# cartePIC_PCR95_8_3_via_res.net
KiCad netlist of a schematic drawn in EAGLE
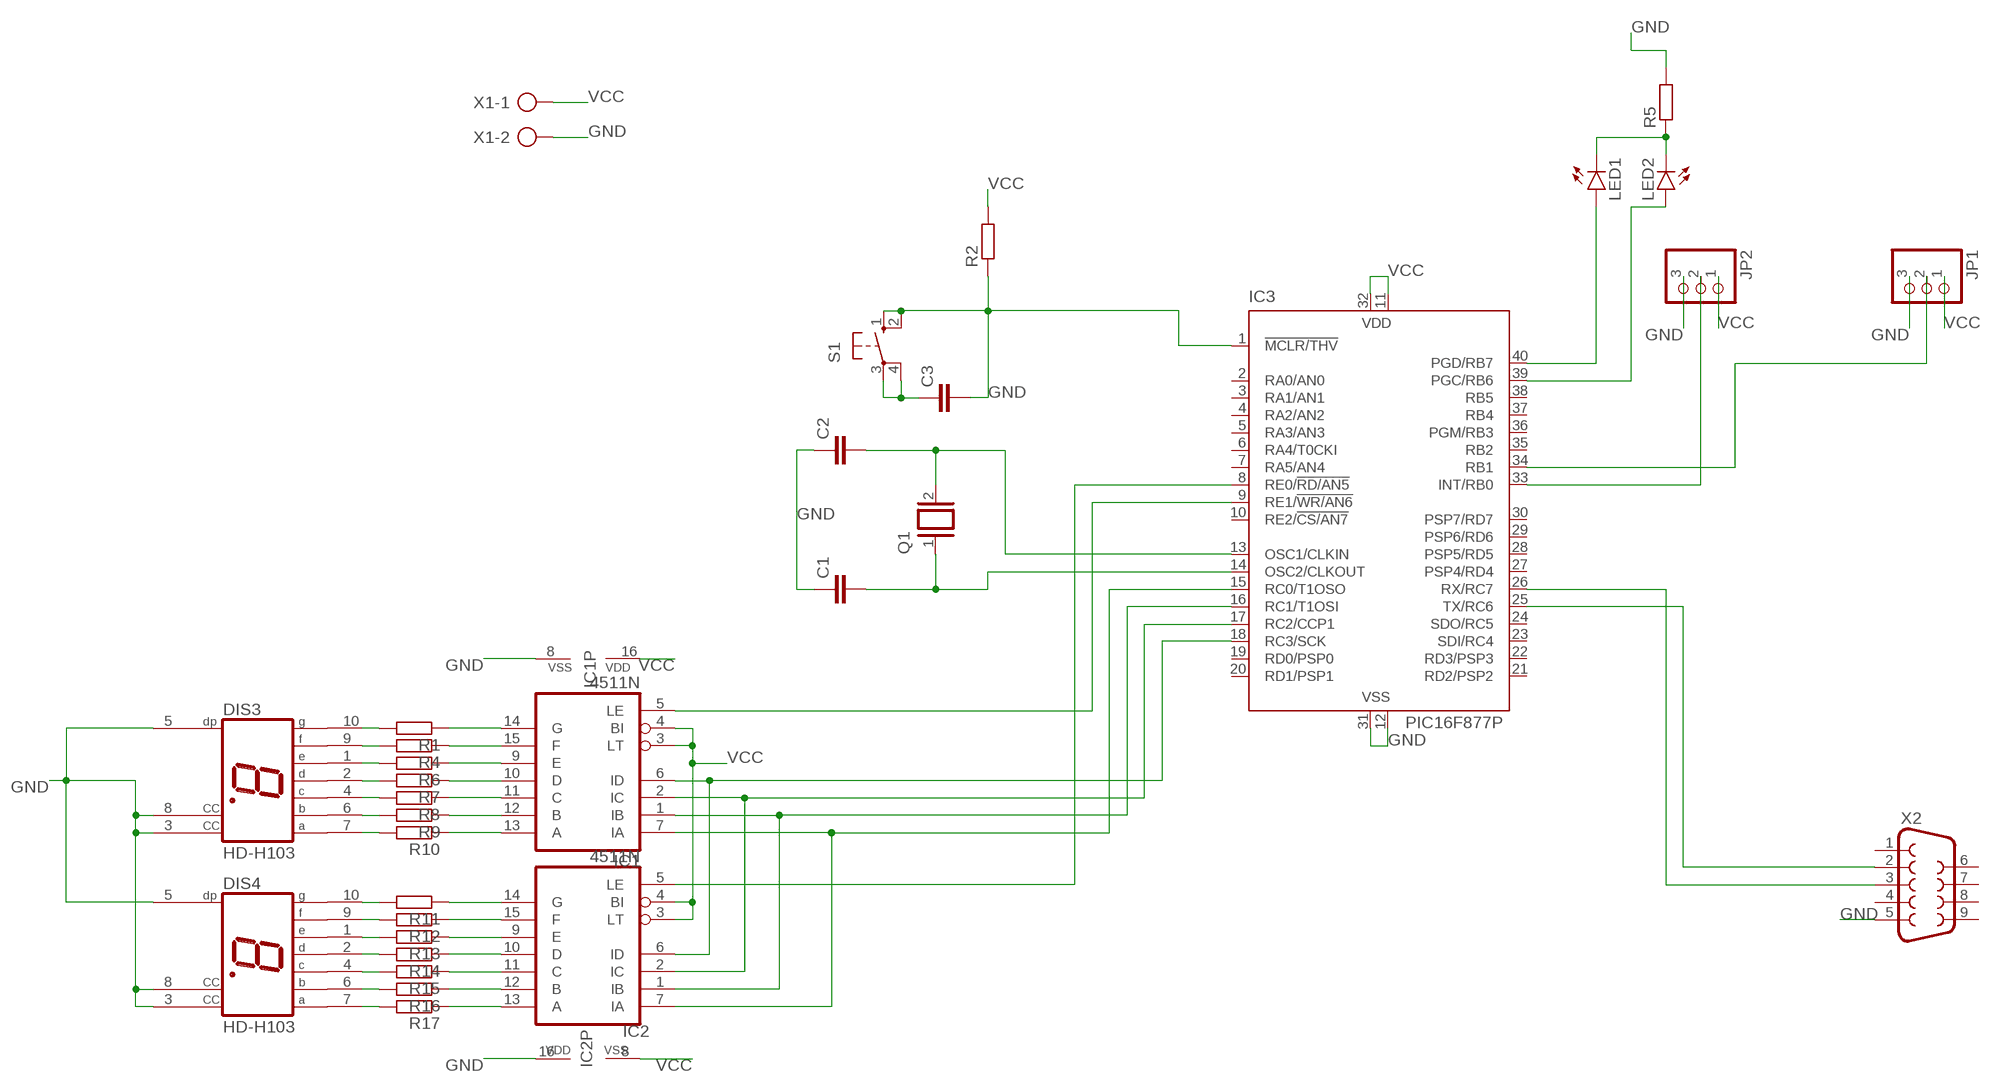
[diagram p0: schematic, sheet 1]

(export (version "E")
  (design (tool "Eeschema 10.0.6"))
  (components
    (comp (ref "C1")
      (value "C-EU025-025X050")
      (footprint "eagle-import:C025-025X050")
      (libsource (lib "eagle-import") (part "C-EU025-025X050"))
    )
    (comp (ref "C2")
      (value "C-EU025-025X050")
      (footprint "eagle-import:C025-025X050")
      (libsource (lib "eagle-import") (part "C-EU025-025X050"))
    )
    (comp (ref "C3")
      (value "C-EU025-025X050")
      (footprint "eagle-import:C025-025X050")
      (libsource (lib "eagle-import") (part "C-EU025-025X050"))
    )
    (comp (ref "DIS3")
      (value "HD-H103")
      (footprint "eagle-import:HDSP-M")
      (libsource (lib "eagle-import") (part "HD-H103"))
    )
    (comp (ref "DIS4")
      (value "HD-H103")
      (footprint "eagle-import:HDSP-M")
      (libsource (lib "eagle-import") (part "HD-H103"))
    )
    (comp (ref "IC1")
      (value "4511N")
      (footprint "eagle-import:DIL16")
      (libsource (lib "eagle-import") (part "4511N"))
    )
    (comp (ref "IC2")
      (value "4511N")
      (footprint "eagle-import:DIL16")
      (libsource (lib "eagle-import") (part "4511N"))
    )
    (comp (ref "IC3")
      (value "PIC16F877P")
      (footprint "eagle-import:DIL40")
      (fields (field (name "MF") "MICROCHIP") (field (name "MPN") "PIC16F877-04/P"))
      (libsource (lib "eagle-import") (part "PIC16F87P7"))
    )
    (comp (ref "JP1")
      (value "PINHD-1X3")
      (footprint "eagle-import:1X03")
      (libsource (lib "eagle-import") (part "PINHD-1X3"))
    )
    (comp (ref "JP2")
      (value "PINHD-1X3")
      (footprint "eagle-import:1X03")
      (libsource (lib "eagle-import") (part "PINHD-1X3"))
    )
    (comp (ref "LED1")
      (value "LED5MM")
      (footprint "eagle-import:LED5MM")
      (libsource (lib "eagle-import") (part "LED5MM"))
    )
    (comp (ref "LED2")
      (value "LED5MM")
      (footprint "eagle-import:LED5MM")
      (libsource (lib "eagle-import") (part "LED5MM"))
    )
    (comp (ref "Q1")
      (value "XTAL/S")
      (footprint "eagle-import:QS")
      (libsource (lib "eagle-import") (part "XTAL/S"))
    )
    (comp (ref "R1")
      (value "R-EU_0207/10")
      (footprint "eagle-import:0207_10")
      (libsource (lib "eagle-import") (part "R-EU_0207/10"))
    )
    (comp (ref "R2")
      (value "R-EU_0207/10")
      (footprint "eagle-import:0207_10")
      (libsource (lib "eagle-import") (part "R-EU_0207/10"))
    )
    (comp (ref "R4")
      (value "R-EU_0207/10")
      (footprint "eagle-import:0207_10")
      (libsource (lib "eagle-import") (part "R-EU_0207/10"))
    )
    (comp (ref "R5")
      (value "R-EU_0207/10")
      (footprint "eagle-import:0207_10")
      (libsource (lib "eagle-import") (part "R-EU_0207/10"))
    )
    (comp (ref "R6")
      (value "R-EU_0207/10")
      (footprint "eagle-import:0207_10")
      (libsource (lib "eagle-import") (part "R-EU_0207/10"))
    )
    (comp (ref "R7")
      (value "R-EU_0207/10")
      (footprint "eagle-import:0207_10")
      (libsource (lib "eagle-import") (part "R-EU_0207/10"))
    )
    (comp (ref "R8")
      (value "R-EU_0207/10")
      (footprint "eagle-import:0207_10")
      (libsource (lib "eagle-import") (part "R-EU_0207/10"))
    )
    (comp (ref "R9")
      (value "R-EU_0207/10")
      (footprint "eagle-import:0207_10")
      (libsource (lib "eagle-import") (part "R-EU_0207/10"))
    )
    (comp (ref "R10")
      (value "R-EU_0207/10")
      (footprint "eagle-import:0207_10")
      (libsource (lib "eagle-import") (part "R-EU_0207/10"))
    )
    (comp (ref "R11")
      (value "R-EU_0207/10")
      (footprint "eagle-import:0207_10")
      (libsource (lib "eagle-import") (part "R-EU_0207/10"))
    )
    (comp (ref "R12")
      (value "R-EU_0207/10")
      (footprint "eagle-import:0207_10")
      (libsource (lib "eagle-import") (part "R-EU_0207/10"))
    )
    (comp (ref "R13")
      (value "R-EU_0207/10")
      (footprint "eagle-import:0207_10")
      (libsource (lib "eagle-import") (part "R-EU_0207/10"))
    )
    (comp (ref "R14")
      (value "R-EU_0207/10")
      (footprint "eagle-import:0207_10")
      (libsource (lib "eagle-import") (part "R-EU_0207/10"))
    )
    (comp (ref "R15")
      (value "R-EU_0207/10")
      (footprint "eagle-import:0207_10")
      (libsource (lib "eagle-import") (part "R-EU_0207/10"))
    )
    (comp (ref "R16")
      (value "R-EU_0207/10")
      (footprint "eagle-import:0207_10")
      (libsource (lib "eagle-import") (part "R-EU_0207/10"))
    )
    (comp (ref "R17")
      (value "R-EU_0207/10")
      (footprint "eagle-import:0207_10")
      (libsource (lib "eagle-import") (part "R-EU_0207/10"))
    )
    (comp (ref "S1")
      (value "10-XX")
      (footprint "eagle-import:B3F-10XX")
      (fields (field (name "MPN") "B3F-1000"))
      (libsource (lib "eagle-import") (part "10-XX"))
    )
    (comp (ref "X1")
      (value "AK300/2")
      (footprint "eagle-import:AK300_2")
      (libsource (lib "eagle-import") (part "AK300/2"))
    )
    (comp (ref "X2")
      (value "F09H")
      (footprint "eagle-import:F09H")
      (libsource (lib "eagle-import") (part "F09H"))
    )
  )
  (nets
    (net (code "1") (name "/GND") (class "Default")
      (node (ref "C1") (pin "1") (pinfunction "1_1") (pintype "passive"))
      (node (ref "C2") (pin "1") (pinfunction "1_1") (pintype "passive"))
      (node (ref "C3") (pin "2") (pinfunction "2_2") (pintype "passive"))
      (node (ref "DIS3") (pin "3") (pinfunction "CC_3") (pintype "passive"))
      (node (ref "DIS3") (pin "5") (pinfunction "DP_5") (pintype "passive"))
      (node (ref "DIS3") (pin "8") (pinfunction "CC_8") (pintype "passive"))
      (node (ref "DIS4") (pin "3") (pinfunction "CC_3") (pintype "passive"))
      (node (ref "DIS4") (pin "5") (pinfunction "DP_5") (pintype "passive"))
      (node (ref "DIS4") (pin "8") (pinfunction "CC_8") (pintype "passive"))
      (node (ref "IC1") (pin "8") (pinfunction "VSS_8") (pintype "power_in"))
      (node (ref "IC2") (pin "16") (pinfunction "VDD_16") (pintype "power_in"))
      (node (ref "IC3") (pin "1") (pinfunction "~{MCLR/THV}_1") (pintype "input"))
      (node (ref "IC3") (pin "12") (pinfunction "VSS_12") (pintype "power_in"))
      (node (ref "IC3") (pin "31") (pinfunction "VSS_31") (pintype "power_in"))
      (node (ref "JP1") (pin "3") (pinfunction "3_3") (pintype "passive"))
      (node (ref "JP2") (pin "3") (pinfunction "3_3") (pintype "passive"))
      (node (ref "R2") (pin "1") (pinfunction "1_1") (pintype "passive"))
      (node (ref "R5") (pin "2") (pinfunction "2_2") (pintype "passive"))
      (node (ref "S1") (pin "1") (pinfunction "S_1") (pintype "passive"))
      (node (ref "S1") (pin "2") (pinfunction "S1_2") (pintype "passive"))
      (node (ref "X1") (pin "2") (pinfunction "KL_2") (pintype "passive"))
      (node (ref "X2") (pin "5") (pinfunction "5_5") (pintype "passive"))
    )
    (net (code "2") (name "/VCC") (class "Default")
      (node (ref "IC1") (pin "16") (pinfunction "VDD_16") (pintype "power_in"))
      (node (ref "IC1") (pin "3") (pinfunction "LT_3") (pintype "input"))
      (node (ref "IC1") (pin "4") (pinfunction "BI_4") (pintype "input"))
      (node (ref "IC2") (pin "3") (pinfunction "LT_3") (pintype "input"))
      (node (ref "IC2") (pin "4") (pinfunction "BI_4") (pintype "input"))
      (node (ref "IC2") (pin "8") (pinfunction "VSS_8") (pintype "power_in"))
      (node (ref "IC3") (pin "11") (pinfunction "VDD_11") (pintype "power_in"))
      (node (ref "IC3") (pin "32") (pinfunction "VDD_32") (pintype "power_in"))
      (node (ref "JP1") (pin "1") (pinfunction "1_1") (pintype "passive"))
      (node (ref "JP2") (pin "1") (pinfunction "1_1") (pintype "passive"))
      (node (ref "R2") (pin "2") (pinfunction "2_2") (pintype "passive"))
      (node (ref "X1") (pin "1") (pinfunction "KL_1") (pintype "passive"))
    )
    (net (code "3") (name "Net-(DIS3-A)") (class "Default")
      (node (ref "DIS3") (pin "7") (pinfunction "A_7") (pintype "passive"))
      (node (ref "R10") (pin "2") (pinfunction "2_2") (pintype "passive"))
    )
    (net (code "4") (name "Net-(DIS3-B)") (class "Default")
      (node (ref "DIS3") (pin "6") (pinfunction "B_6") (pintype "passive"))
      (node (ref "R9") (pin "2") (pinfunction "2_2") (pintype "passive"))
    )
    (net (code "5") (name "Net-(DIS3-C)") (class "Default")
      (node (ref "DIS3") (pin "4") (pinfunction "C_4") (pintype "passive"))
      (node (ref "R8") (pin "2") (pinfunction "2_2") (pintype "passive"))
    )
    (net (code "6") (name "Net-(DIS3-D)") (class "Default")
      (node (ref "DIS3") (pin "2") (pinfunction "D_2") (pintype "passive"))
      (node (ref "R7") (pin "2") (pinfunction "2_2") (pintype "passive"))
    )
    (net (code "7") (name "Net-(DIS3-E)") (class "Default")
      (node (ref "DIS3") (pin "1") (pinfunction "E_1") (pintype "passive"))
      (node (ref "R6") (pin "2") (pinfunction "2_2") (pintype "passive"))
    )
    (net (code "8") (name "Net-(DIS3-F)") (class "Default")
      (node (ref "DIS3") (pin "9") (pinfunction "F_9") (pintype "passive"))
      (node (ref "R4") (pin "2") (pinfunction "2_2") (pintype "passive"))
    )
    (net (code "9") (name "Net-(DIS3-G)") (class "Default")
      (node (ref "DIS3") (pin "10") (pinfunction "G_10") (pintype "passive"))
      (node (ref "R1") (pin "2") (pinfunction "2_2") (pintype "passive"))
    )
    (net (code "10") (name "Net-(DIS4-A)") (class "Default")
      (node (ref "DIS4") (pin "7") (pinfunction "A_7") (pintype "passive"))
      (node (ref "R17") (pin "2") (pinfunction "2_2") (pintype "passive"))
    )
    (net (code "11") (name "Net-(DIS4-B)") (class "Default")
      (node (ref "DIS4") (pin "6") (pinfunction "B_6") (pintype "passive"))
      (node (ref "R16") (pin "2") (pinfunction "2_2") (pintype "passive"))
    )
    (net (code "12") (name "Net-(DIS4-C)") (class "Default")
      (node (ref "DIS4") (pin "4") (pinfunction "C_4") (pintype "passive"))
      (node (ref "R15") (pin "2") (pinfunction "2_2") (pintype "passive"))
    )
    (net (code "13") (name "Net-(DIS4-D)") (class "Default")
      (node (ref "DIS4") (pin "2") (pinfunction "D_2") (pintype "passive"))
      (node (ref "R14") (pin "2") (pinfunction "2_2") (pintype "passive"))
    )
    (net (code "14") (name "Net-(DIS4-E)") (class "Default")
      (node (ref "DIS4") (pin "1") (pinfunction "E_1") (pintype "passive"))
      (node (ref "R13") (pin "2") (pinfunction "2_2") (pintype "passive"))
    )
    (net (code "15") (name "Net-(DIS4-F)") (class "Default")
      (node (ref "DIS4") (pin "9") (pinfunction "F_9") (pintype "passive"))
      (node (ref "R12") (pin "2") (pinfunction "2_2") (pintype "passive"))
    )
    (net (code "16") (name "Net-(DIS4-G)") (class "Default")
      (node (ref "DIS4") (pin "10") (pinfunction "G_10") (pintype "passive"))
      (node (ref "R11") (pin "2") (pinfunction "2_2") (pintype "passive"))
    )
    (net (code "17") (name "Net-(IC1A-A)") (class "Default")
      (node (ref "IC1") (pin "13") (pinfunction "A_13") (pintype "output"))
      (node (ref "R10") (pin "1") (pinfunction "1_1") (pintype "passive"))
    )
    (net (code "18") (name "Net-(IC1A-B)") (class "Default")
      (node (ref "IC1") (pin "12") (pinfunction "B_12") (pintype "output"))
      (node (ref "R9") (pin "1") (pinfunction "1_1") (pintype "passive"))
    )
    (net (code "19") (name "Net-(IC1A-C)") (class "Default")
      (node (ref "IC1") (pin "11") (pinfunction "C_11") (pintype "output"))
      (node (ref "R8") (pin "1") (pinfunction "1_1") (pintype "passive"))
    )
    (net (code "20") (name "Net-(IC1A-D)") (class "Default")
      (node (ref "IC1") (pin "10") (pinfunction "D_10") (pintype "output"))
      (node (ref "R7") (pin "1") (pinfunction "1_1") (pintype "passive"))
    )
    (net (code "21") (name "Net-(IC1A-E)") (class "Default")
      (node (ref "IC1") (pin "9") (pinfunction "E_9") (pintype "output"))
      (node (ref "R6") (pin "1") (pinfunction "1_1") (pintype "passive"))
    )
    (net (code "22") (name "Net-(IC1A-F)") (class "Default")
      (node (ref "IC1") (pin "15") (pinfunction "F_15") (pintype "output"))
      (node (ref "R4") (pin "1") (pinfunction "1_1") (pintype "passive"))
    )
    (net (code "23") (name "Net-(IC1A-G)") (class "Default")
      (node (ref "IC1") (pin "14") (pinfunction "G_14") (pintype "output"))
      (node (ref "R1") (pin "1") (pinfunction "1_1") (pintype "passive"))
    )
    (net (code "24") (name "Net-(IC1A-IA)") (class "Default")
      (node (ref "IC1") (pin "7") (pinfunction "IA_7") (pintype "input"))
      (node (ref "IC2") (pin "7") (pinfunction "IA_7") (pintype "input"))
      (node (ref "IC3") (pin "15") (pinfunction "RC0/T1OSO_15") (pintype "bidirectional"))
    )
    (net (code "25") (name "Net-(IC1A-IB)") (class "Default")
      (node (ref "IC1") (pin "1") (pinfunction "IB_1") (pintype "input"))
      (node (ref "IC2") (pin "1") (pinfunction "IB_1") (pintype "input"))
      (node (ref "IC3") (pin "16") (pinfunction "RC1/T1OSI_16") (pintype "bidirectional"))
    )
    (net (code "26") (name "Net-(IC1A-IC)") (class "Default")
      (node (ref "IC1") (pin "2") (pinfunction "IC_2") (pintype "input"))
      (node (ref "IC2") (pin "2") (pinfunction "IC_2") (pintype "input"))
      (node (ref "IC3") (pin "17") (pinfunction "RC2/CCP1_17") (pintype "bidirectional"))
    )
    (net (code "27") (name "Net-(IC1A-ID)") (class "Default")
      (node (ref "IC1") (pin "6") (pinfunction "ID_6") (pintype "input"))
      (node (ref "IC2") (pin "6") (pinfunction "ID_6") (pintype "input"))
      (node (ref "IC3") (pin "18") (pinfunction "RC3/SCK_18") (pintype "bidirectional"))
    )
    (net (code "28") (name "Net-(IC1A-LE)") (class "Default")
      (node (ref "IC1") (pin "5") (pinfunction "LE_5") (pintype "input"))
      (node (ref "IC3") (pin "9") (pinfunction "RE1/~{WR/AN6}_9") (pintype "bidirectional"))
    )
    (net (code "29") (name "Net-(IC2A-A)") (class "Default")
      (node (ref "IC2") (pin "13") (pinfunction "A_13") (pintype "output"))
      (node (ref "R17") (pin "1") (pinfunction "1_1") (pintype "passive"))
    )
    (net (code "30") (name "Net-(IC2A-B)") (class "Default")
      (node (ref "IC2") (pin "12") (pinfunction "B_12") (pintype "output"))
      (node (ref "R16") (pin "1") (pinfunction "1_1") (pintype "passive"))
    )
    (net (code "31") (name "Net-(IC2A-C)") (class "Default")
      (node (ref "IC2") (pin "11") (pinfunction "C_11") (pintype "output"))
      (node (ref "R15") (pin "1") (pinfunction "1_1") (pintype "passive"))
    )
    (net (code "32") (name "Net-(IC2A-D)") (class "Default")
      (node (ref "IC2") (pin "10") (pinfunction "D_10") (pintype "output"))
      (node (ref "R14") (pin "1") (pinfunction "1_1") (pintype "passive"))
    )
    (net (code "33") (name "Net-(IC2A-E)") (class "Default")
      (node (ref "IC2") (pin "9") (pinfunction "E_9") (pintype "output"))
      (node (ref "R13") (pin "1") (pinfunction "1_1") (pintype "passive"))
    )
    (net (code "34") (name "Net-(IC2A-F)") (class "Default")
      (node (ref "IC2") (pin "15") (pinfunction "F_15") (pintype "output"))
      (node (ref "R12") (pin "1") (pinfunction "1_1") (pintype "passive"))
    )
    (net (code "35") (name "Net-(IC2A-G)") (class "Default")
      (node (ref "IC2") (pin "14") (pinfunction "G_14") (pintype "output"))
      (node (ref "R11") (pin "1") (pinfunction "1_1") (pintype "passive"))
    )
    (net (code "36") (name "Net-(IC2A-LE)") (class "Default")
      (node (ref "IC2") (pin "5") (pinfunction "LE_5") (pintype "input"))
      (node (ref "IC3") (pin "8") (pinfunction "RE0/~{RD/AN5}_8") (pintype "bidirectional"))
    )
    (net (code "37") (name "Net-(IC3-INT{slash}RB0)") (class "Default")
      (node (ref "IC3") (pin "33") (pinfunction "INT/RB0_33") (pintype "bidirectional"))
      (node (ref "JP2") (pin "2") (pinfunction "2_2") (pintype "passive"))
    )
    (net (code "38") (name "Net-(IC3-OSC1{slash}CLKIN)") (class "Default")
      (node (ref "C2") (pin "2") (pinfunction "2_2") (pintype "passive"))
      (node (ref "IC3") (pin "13") (pinfunction "OSC1/CLKIN_13") (pintype "input"))
      (node (ref "Q1") (pin "2") (pinfunction "2_2") (pintype "passive"))
    )
    (net (code "39") (name "Net-(IC3-OSC2{slash}CLKOUT)") (class "Default")
      (node (ref "C1") (pin "2") (pinfunction "2_2") (pintype "passive"))
      (node (ref "IC3") (pin "14") (pinfunction "OSC2/CLKOUT_14") (pintype "output"))
      (node (ref "Q1") (pin "1") (pinfunction "1_1") (pintype "passive"))
    )
    (net (code "40") (name "Net-(IC3-PGC{slash}RB6)") (class "Default")
      (node (ref "IC3") (pin "39") (pinfunction "PGC/RB6_39") (pintype "bidirectional"))
      (node (ref "LED2") (pin "A") (pinfunction "A_A") (pintype "passive"))
    )
    (net (code "41") (name "Net-(IC3-PGD{slash}RB7)") (class "Default")
      (node (ref "IC3") (pin "40") (pinfunction "PGD/RB7_40") (pintype "bidirectional"))
      (node (ref "LED1") (pin "A") (pinfunction "A_A") (pintype "passive"))
    )
    (net (code "42") (name "Net-(IC3-RB1)") (class "Default")
      (node (ref "IC3") (pin "34") (pinfunction "RB1_34") (pintype "bidirectional"))
      (node (ref "JP1") (pin "2") (pinfunction "2_2") (pintype "passive"))
    )
    (net (code "43") (name "Net-(IC3-RX{slash}RC7)") (class "Default")
      (node (ref "IC3") (pin "26") (pinfunction "RX/RC7_26") (pintype "bidirectional"))
      (node (ref "X2") (pin "3") (pinfunction "3_3") (pintype "passive"))
    )
    (net (code "44") (name "Net-(IC3-TX{slash}RC6)") (class "Default")
      (node (ref "IC3") (pin "25") (pinfunction "TX/RC6_25") (pintype "bidirectional"))
      (node (ref "X2") (pin "2") (pinfunction "2_2") (pintype "passive"))
    )
    (net (code "45") (name "Net-(LED1-C)") (class "Default")
      (node (ref "LED1") (pin "K") (pinfunction "C_K") (pintype "passive"))
      (node (ref "LED2") (pin "K") (pinfunction "C_K") (pintype "passive"))
      (node (ref "R5") (pin "1") (pinfunction "1_1") (pintype "passive"))
    )
    (net (code "46") (name "Net-(S1-P)") (class "Default")
      (node (ref "C3") (pin "1") (pinfunction "1_1") (pintype "passive"))
      (node (ref "S1") (pin "3") (pinfunction "P_3") (pintype "passive"))
      (node (ref "S1") (pin "4") (pinfunction "P1_4") (pintype "passive"))
    )
    (net (code "47") (name "unconnected-(IC3-PGM{slash}RB3-Pad36)") (class "Default")
      (node (ref "IC3") (pin "36") (pinfunction "PGM/RB3_36") (pintype "bidirectional"))
    )
    (net (code "48") (name "unconnected-(IC3-PSP4{slash}RD4-Pad27)") (class "Default")
      (node (ref "IC3") (pin "27") (pinfunction "PSP4/RD4_27") (pintype "bidirectional"))
    )
    (net (code "49") (name "unconnected-(IC3-PSP5{slash}RD5-Pad28)") (class "Default")
      (node (ref "IC3") (pin "28") (pinfunction "PSP5/RD5_28") (pintype "bidirectional"))
    )
    (net (code "50") (name "unconnected-(IC3-PSP6{slash}RD6-Pad29)") (class "Default")
      (node (ref "IC3") (pin "29") (pinfunction "PSP6/RD6_29") (pintype "bidirectional"))
    )
    (net (code "51") (name "unconnected-(IC3-PSP7{slash}RD7-Pad30)") (class "Default")
      (node (ref "IC3") (pin "30") (pinfunction "PSP7/RD7_30") (pintype "bidirectional"))
    )
    (net (code "52") (name "unconnected-(IC3-RA0{slash}AN0-Pad2)") (class "Default")
      (node (ref "IC3") (pin "2") (pinfunction "RA0/AN0_2") (pintype "bidirectional"))
    )
    (net (code "53") (name "unconnected-(IC3-RA1{slash}AN1-Pad3)") (class "Default")
      (node (ref "IC3") (pin "3") (pinfunction "RA1/AN1_3") (pintype "bidirectional"))
    )
    (net (code "54") (name "unconnected-(IC3-RA2{slash}AN2-Pad4)") (class "Default")
      (node (ref "IC3") (pin "4") (pinfunction "RA2/AN2_4") (pintype "bidirectional"))
    )
    (net (code "55") (name "unconnected-(IC3-RA3{slash}AN3-Pad5)") (class "Default")
      (node (ref "IC3") (pin "5") (pinfunction "RA3/AN3_5") (pintype "bidirectional"))
    )
    (net (code "56") (name "unconnected-(IC3-RA4{slash}T0CKI-Pad6)") (class "Default")
      (node (ref "IC3") (pin "6") (pinfunction "RA4/T0CKI_6") (pintype "bidirectional"))
    )
    (net (code "57") (name "unconnected-(IC3-RA5{slash}AN4-Pad7)") (class "Default")
      (node (ref "IC3") (pin "7") (pinfunction "RA5/AN4_7") (pintype "bidirectional"))
    )
    (net (code "58") (name "unconnected-(IC3-RB2-Pad35)") (class "Default")
      (node (ref "IC3") (pin "35") (pinfunction "RB2_35") (pintype "bidirectional"))
    )
    (net (code "59") (name "unconnected-(IC3-RB4-Pad37)") (class "Default")
      (node (ref "IC3") (pin "37") (pinfunction "RB4_37") (pintype "bidirectional"))
    )
    (net (code "60") (name "unconnected-(IC3-RB5-Pad38)") (class "Default")
      (node (ref "IC3") (pin "38") (pinfunction "RB5_38") (pintype "bidirectional"))
    )
    (net (code "61") (name "unconnected-(IC3-RD0{slash}PSP0-Pad19)") (class "Default")
      (node (ref "IC3") (pin "19") (pinfunction "RD0/PSP0_19") (pintype "bidirectional"))
    )
    (net (code "62") (name "unconnected-(IC3-RD1{slash}PSP1-Pad20)") (class "Default")
      (node (ref "IC3") (pin "20") (pinfunction "RD1/PSP1_20") (pintype "bidirectional"))
    )
    (net (code "63") (name "unconnected-(IC3-RD2{slash}PSP2-Pad21)") (class "Default")
      (node (ref "IC3") (pin "21") (pinfunction "RD2/PSP2_21") (pintype "bidirectional"))
    )
    (net (code "64") (name "unconnected-(IC3-RD3{slash}PSP3-Pad22)") (class "Default")
      (node (ref "IC3") (pin "22") (pinfunction "RD3/PSP3_22") (pintype "bidirectional"))
    )
    (net (code "65") (name "unconnected-(IC3-RE2{slash}~{CS{slash}AN7}-Pad10)") (class "Default")
      (node (ref "IC3") (pin "10") (pinfunction "RE2/~{CS/AN7}_10") (pintype "bidirectional"))
    )
    (net (code "66") (name "unconnected-(IC3-SDI{slash}RC4-Pad23)") (class "Default")
      (node (ref "IC3") (pin "23") (pinfunction "SDI/RC4_23") (pintype "bidirectional"))
    )
    (net (code "67") (name "unconnected-(IC3-SDO{slash}RC5-Pad24)") (class "Default")
      (node (ref "IC3") (pin "24") (pinfunction "SDO/RC5_24") (pintype "bidirectional"))
    )
    (net (code "68") (name "unconnected-(X2-Pad1)") (class "Default")
      (node (ref "X2") (pin "1") (pinfunction "1_1") (pintype "passive"))
    )
    (net (code "69") (name "unconnected-(X2-Pad4)") (class "Default")
      (node (ref "X2") (pin "4") (pinfunction "4_4") (pintype "passive"))
    )
    (net (code "70") (name "unconnected-(X2-Pad6)") (class "Default")
      (node (ref "X2") (pin "6") (pinfunction "6_6") (pintype "passive"))
    )
    (net (code "71") (name "unconnected-(X2-Pad7)") (class "Default")
      (node (ref "X2") (pin "7") (pinfunction "7_7") (pintype "passive"))
    )
    (net (code "72") (name "unconnected-(X2-Pad8)") (class "Default")
      (node (ref "X2") (pin "8") (pinfunction "8_8") (pintype "passive"))
    )
    (net (code "73") (name "unconnected-(X2-Pad9)") (class "Default")
      (node (ref "X2") (pin "9") (pinfunction "9_9") (pintype "passive"))
    )
  )
)
